# LORA_ANT.net
KiCad netlist of a schematic drawn in Altium Designer
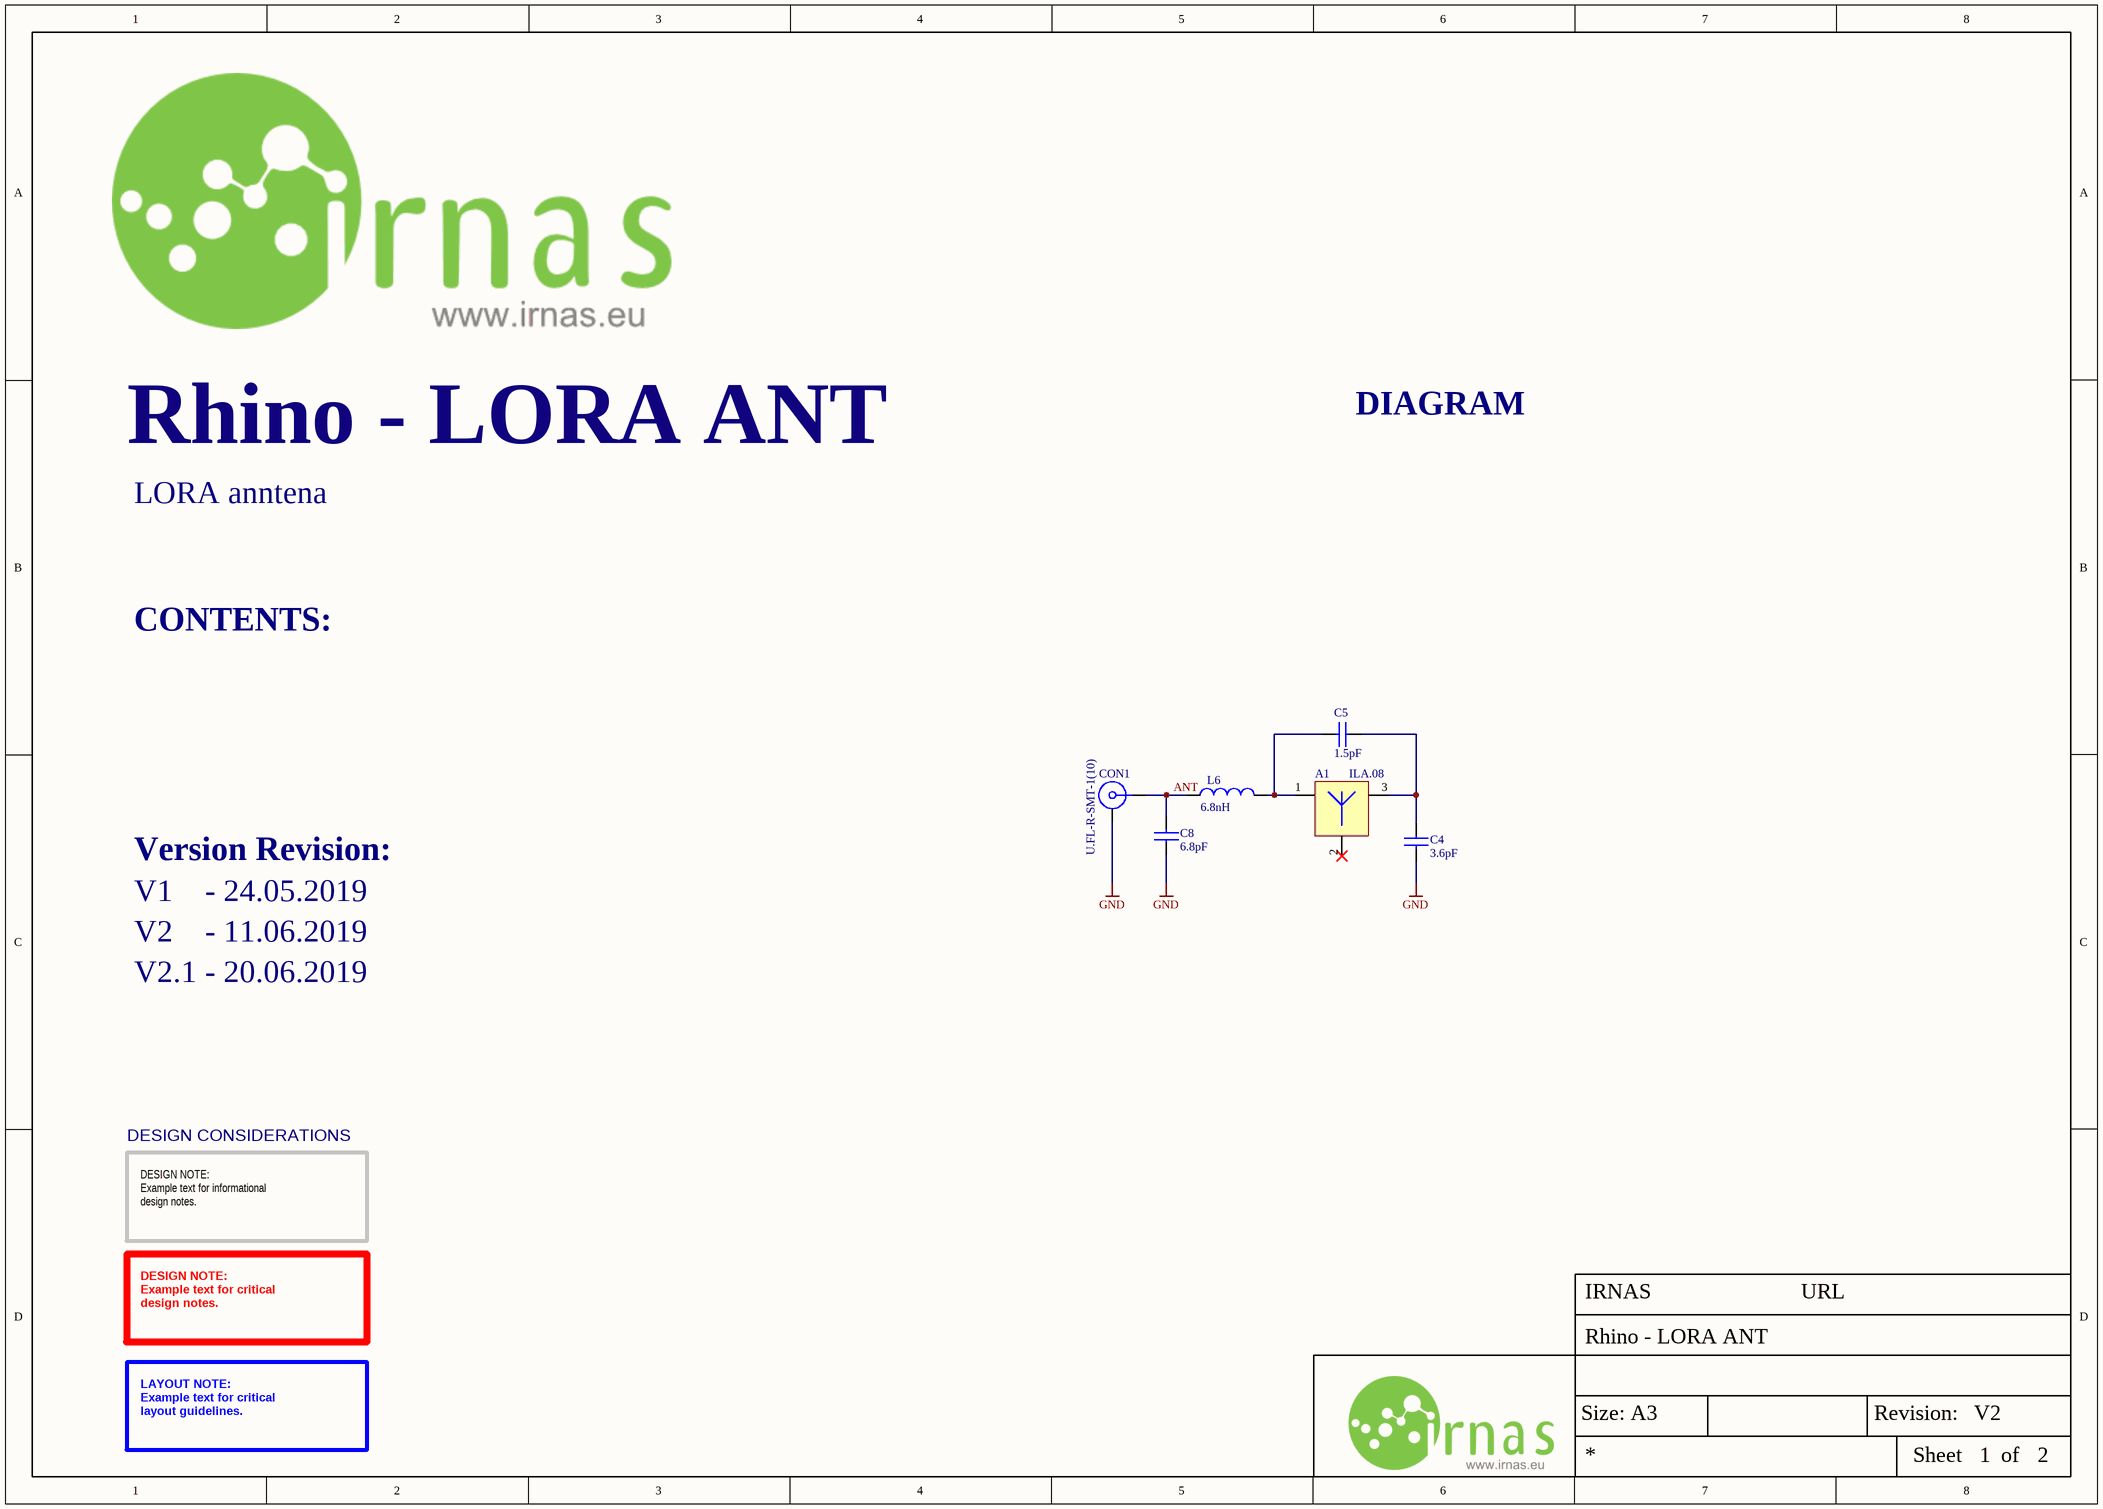
[diagram p0: LORA_ANT.SchDoc]

(export (version "E")
  (design (tool "Eeschema 10.0.6"))
  (components
    (comp (ref "A1")
      (value "ILA.08")
      (footprint "ILA.08_LORA")
      (description "Antenna, ISM/Lora/Lpwan/Sigfox, 868Mhz Center Frequency, 5mm x 3mm x 0.5mm Dimensions")
      (fields (field (name "MANUFACTURER") "Antenova") (field (name "MANUFACTURER PART NUMBER") "SR42I010-R"))
      (libsource (lib "Passive") (part "ANT - ILA.08"))
    )
    (comp (ref "C4")
      (value "3.6pF")
      (footprint "CAP0402")
      (description "Multilayer Ceramic Capacitors MLCC - SMD/SMT 50volts 1.8pF C0G")
      (fields
        (field (name "MANUFACTURER") "KEMET")
        (field (name "MANUFACTURER PART NUMBER") "C0402C189B5GACTU")
      )
      (libsource (lib "Passive") (part "C - 1.8pF/0402"))
    )
    (comp (ref "C5")
      (value "1.5pF")
      (footprint "CAP0402")
      (description "Multilayer Ceramic Capacitors MLCC - SMD/SMT 50volts 1.8pF C0G")
      (fields
        (field (name "MANUFACTURER") "KEMET")
        (field (name "MANUFACTURER PART NUMBER") "C0402C189B5GACTU")
      )
      (libsource (lib "Passive") (part "C - 1.8pF/0402"))
    )
    (comp (ref "C8")
      (value "6.8pF")
      (footprint "CAP0402")
      (description "Multilayer Ceramic Capacitors MLCC - SMD/SMT 50volts 1.8pF C0G")
      (fields
        (field (name "MANUFACTURER") "KEMET")
        (field (name "MANUFACTURER PART NUMBER") "C0402C189B5GACTU")
      )
      (libsource (lib "Passive") (part "C - 1.8pF/0402"))
    )
    (comp (ref "CON1")
      (value "U.FL-R-SMT-1(10)")
      (footprint "ufl connector smd")
      (description "RF / Coaxial Connector, U.FL Coaxial, Straight Jack, Surface Mount Vertical, 50 ohm, Brass")
      (fields (field (name "MANUFACTURER") "Hirose"))
      (libsource (lib "Connectors") (part "U.FL-R-SMT-1(10)"))
    )
    (comp (ref "L6")
      (value "6.8nH")
      (footprint "IND0402")
      (description "Inductor RF Chip Multi-Layer 4.3nH 0.3nH 100MHz 8Q-Factor Air 300mA 210mOhm DCR 0402 Paper T/R")
      (fields
        (field (name "MANUFACTURER") "Murata")
        (field (name "MANUFACTURER PART NUMBER") "LQG15HN4N3S02D")
      )
      (libsource (lib "Passive") (part "L - 4.3nH/0402"))
    )
  )
  (nets
    (net (code "1") (name "/ANT") (class "Default")
      (node (ref "C8") (pin "2") (pinfunction "2_2") (pintype "passive"))
      (node (ref "CON1") (pin "1") (pinfunction "1_1") (pintype "open_collector"))
      (node (ref "L6") (pin "1") (pinfunction "1_1") (pintype "passive"))
    )
    (net (code "2") (name "GND") (class "Default")
      (node (ref "C4") (pin "2") (pinfunction "2_2") (pintype "passive"))
      (node (ref "C8") (pin "1") (pinfunction "1_1") (pintype "passive"))
      (node (ref "CON1") (pin "2") (pinfunction "2_2") (pintype "open_collector"))
    )
    (net (code "3") (name "Net-(A1-Pad1)") (class "Default")
      (node (ref "A1") (pin "1") (pinfunction "1_1") (pintype "passive"))
      (node (ref "C5") (pin "2") (pinfunction "2_2") (pintype "passive"))
      (node (ref "L6") (pin "2") (pinfunction "2_2") (pintype "passive"))
    )
    (net (code "4") (name "Net-(A1-Pad3)") (class "Default")
      (node (ref "A1") (pin "3") (pinfunction "3_3") (pintype "passive"))
      (node (ref "C4") (pin "1") (pinfunction "1_1") (pintype "passive"))
      (node (ref "C5") (pin "1") (pinfunction "1_1") (pintype "passive"))
    )
    (net (code "5") (name "unconnected-(A1-Pad2)") (class "Default")
      (node (ref "A1") (pin "2") (pinfunction "2_2") (pintype "passive+no_connect"))
    )
  )
)
